# fpga-ground-inside.net
KiCad netlist of a schematic drawn in Altium Designer
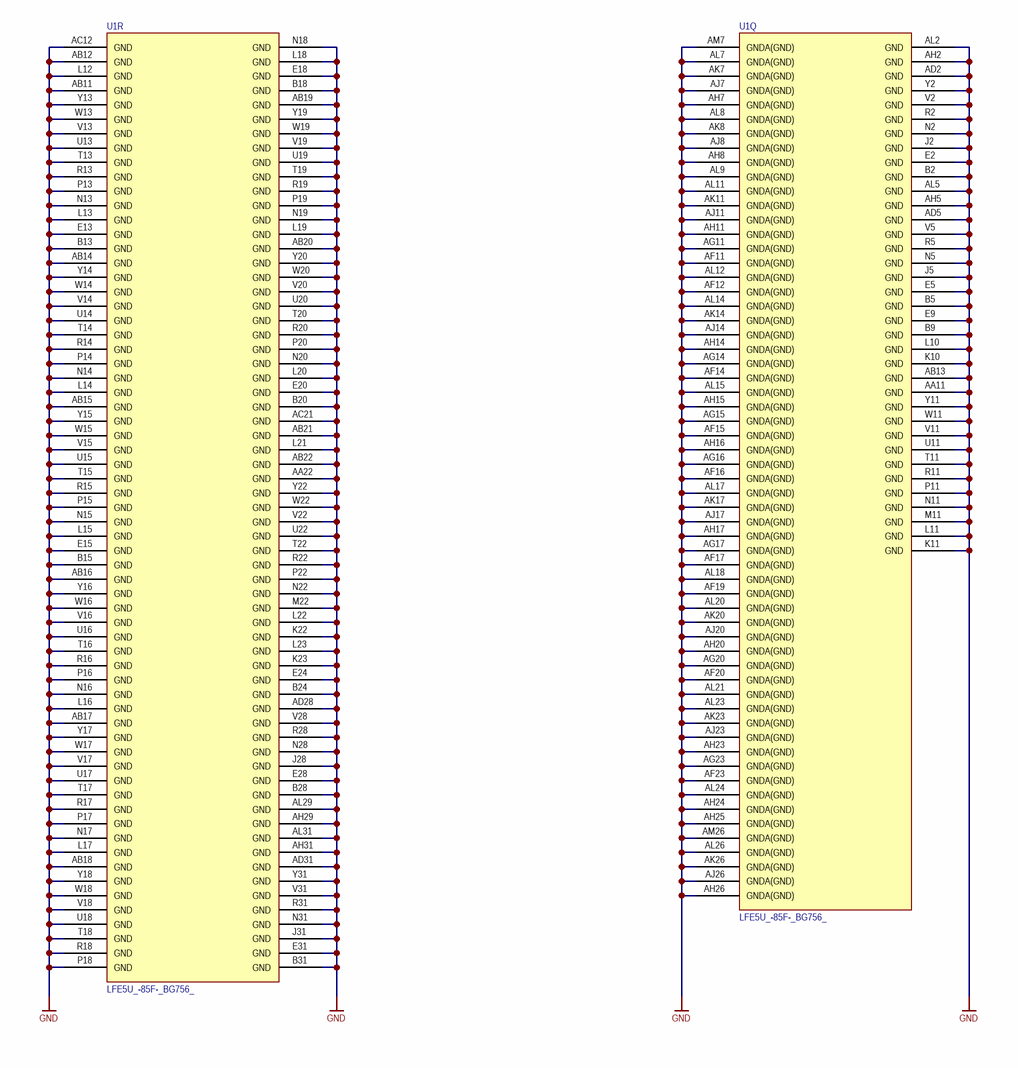
[diagram p0: fpga-ground-inside.SchDoc]

(export (version "E")
  (design (tool "Eeschema 10.0.6"))
  (components
    (comp (ref "U1")
      (value "LFE5U_-85F-_BG756_")
      (footprint "lattice:caBGA756")
      (description "ECP5 FPGA, 85k LUT, 756-caBGA")
      (fields (field (name "MANUFACTURER") "Lattice Semiconductor"))
      (libsource (lib "lattice") (part "LFE5U_-85F-_BG756_"))
    )
  )
  (nets
    (net (code "1") (name "GND") (class "Default")
      (node (ref "U1") (pin "AA11") (pinfunction "GND_AA11") (pintype "power_in"))
      (node (ref "U1") (pin "AA22") (pinfunction "GND_AA22") (pintype "power_in"))
      (node (ref "U1") (pin "AB11") (pinfunction "GND_AB11") (pintype "power_in"))
      (node (ref "U1") (pin "AB12") (pinfunction "GND_AB12") (pintype "power_in"))
      (node (ref "U1") (pin "AB13") (pinfunction "GND_AB13") (pintype "power_in"))
      (node (ref "U1") (pin "AB14") (pinfunction "GND_AB14") (pintype "power_in"))
      (node (ref "U1") (pin "AB15") (pinfunction "GND_AB15") (pintype "power_in"))
      (node (ref "U1") (pin "AB16") (pinfunction "GND_AB16") (pintype "power_in"))
      (node (ref "U1") (pin "AB17") (pinfunction "GND_AB17") (pintype "power_in"))
      (node (ref "U1") (pin "AB18") (pinfunction "GND_AB18") (pintype "power_in"))
      (node (ref "U1") (pin "AB19") (pinfunction "GND_AB19") (pintype "power_in"))
      (node (ref "U1") (pin "AB20") (pinfunction "GND_AB20") (pintype "power_in"))
      (node (ref "U1") (pin "AB21") (pinfunction "GND_AB21") (pintype "power_in"))
      (node (ref "U1") (pin "AB22") (pinfunction "GND_AB22") (pintype "power_in"))
      (node (ref "U1") (pin "AC12") (pinfunction "GND_AC12") (pintype "power_in"))
      (node (ref "U1") (pin "AC21") (pinfunction "GND_AC21") (pintype "power_in"))
      (node (ref "U1") (pin "AD2") (pinfunction "GND_AD2") (pintype "power_in"))
      (node (ref "U1") (pin "AD28") (pinfunction "GND_AD28") (pintype "power_in"))
      (node (ref "U1") (pin "AD31") (pinfunction "GND_AD31") (pintype "power_in"))
      (node (ref "U1") (pin "AD5") (pinfunction "GND_AD5") (pintype "power_in"))
      (node (ref "U1") (pin "AF11") (pinfunction "GNDA(GND)_AF11") (pintype "power_in"))
      (node (ref "U1") (pin "AF12") (pinfunction "GNDA(GND)_AF12") (pintype "power_in"))
      (node (ref "U1") (pin "AF14") (pinfunction "GNDA(GND)_AF14") (pintype "power_in"))
      (node (ref "U1") (pin "AF15") (pinfunction "GNDA(GND)_AF15") (pintype "power_in"))
      (node (ref "U1") (pin "AF16") (pinfunction "GNDA(GND)_AF16") (pintype "power_in"))
      (node (ref "U1") (pin "AF17") (pinfunction "GNDA(GND)_AF17") (pintype "power_in"))
      (node (ref "U1") (pin "AF19") (pinfunction "GNDA(GND)_AF19") (pintype "power_in"))
      (node (ref "U1") (pin "AF20") (pinfunction "GNDA(GND)_AF20") (pintype "power_in"))
      (node (ref "U1") (pin "AF23") (pinfunction "GNDA(GND)_AF23") (pintype "power_in"))
      (node (ref "U1") (pin "AG11") (pinfunction "GNDA(GND)_AG11") (pintype "power_in"))
      (node (ref "U1") (pin "AG14") (pinfunction "GNDA(GND)_AG14") (pintype "power_in"))
      (node (ref "U1") (pin "AG15") (pinfunction "GNDA(GND)_AG15") (pintype "power_in"))
      (node (ref "U1") (pin "AG16") (pinfunction "GNDA(GND)_AG16") (pintype "power_in"))
      (node (ref "U1") (pin "AG17") (pinfunction "GNDA(GND)_AG17") (pintype "power_in"))
      (node (ref "U1") (pin "AG20") (pinfunction "GNDA(GND)_AG20") (pintype "power_in"))
      (node (ref "U1") (pin "AG23") (pinfunction "GNDA(GND)_AG23") (pintype "power_in"))
      (node (ref "U1") (pin "AH11") (pinfunction "GNDA(GND)_AH11") (pintype "power_in"))
      (node (ref "U1") (pin "AH14") (pinfunction "GNDA(GND)_AH14") (pintype "power_in"))
      (node (ref "U1") (pin "AH15") (pinfunction "GNDA(GND)_AH15") (pintype "power_in"))
      (node (ref "U1") (pin "AH16") (pinfunction "GNDA(GND)_AH16") (pintype "power_in"))
      (node (ref "U1") (pin "AH17") (pinfunction "GNDA(GND)_AH17") (pintype "power_in"))
      (node (ref "U1") (pin "AH2") (pinfunction "GND_AH2") (pintype "power_in"))
      (node (ref "U1") (pin "AH20") (pinfunction "GNDA(GND)_AH20") (pintype "power_in"))
      (node (ref "U1") (pin "AH23") (pinfunction "GNDA(GND)_AH23") (pintype "power_in"))
      (node (ref "U1") (pin "AH24") (pinfunction "GNDA(GND)_AH24") (pintype "power_in"))
      (node (ref "U1") (pin "AH25") (pinfunction "GNDA(GND)_AH25") (pintype "power_in"))
      (node (ref "U1") (pin "AH26") (pinfunction "GNDA(GND)_AH26") (pintype "power_in"))
      (node (ref "U1") (pin "AH29") (pinfunction "GND_AH29") (pintype "power_in"))
      (node (ref "U1") (pin "AH31") (pinfunction "GND_AH31") (pintype "power_in"))
      (node (ref "U1") (pin "AH5") (pinfunction "GND_AH5") (pintype "power_in"))
      (node (ref "U1") (pin "AH7") (pinfunction "GNDA(GND)_AH7") (pintype "power_in"))
      (node (ref "U1") (pin "AH8") (pinfunction "GNDA(GND)_AH8") (pintype "power_in"))
      (node (ref "U1") (pin "AJ11") (pinfunction "GNDA(GND)_AJ11") (pintype "power_in"))
      (node (ref "U1") (pin "AJ14") (pinfunction "GNDA(GND)_AJ14") (pintype "power_in"))
      (node (ref "U1") (pin "AJ17") (pinfunction "GNDA(GND)_AJ17") (pintype "power_in"))
      (node (ref "U1") (pin "AJ20") (pinfunction "GNDA(GND)_AJ20") (pintype "power_in"))
      (node (ref "U1") (pin "AJ23") (pinfunction "GNDA(GND)_AJ23") (pintype "power_in"))
      (node (ref "U1") (pin "AJ26") (pinfunction "GNDA(GND)_AJ26") (pintype "power_in"))
      (node (ref "U1") (pin "AJ7") (pinfunction "GNDA(GND)_AJ7") (pintype "power_in"))
      (node (ref "U1") (pin "AJ8") (pinfunction "GNDA(GND)_AJ8") (pintype "power_in"))
      (node (ref "U1") (pin "AK11") (pinfunction "GNDA(GND)_AK11") (pintype "power_in"))
      (node (ref "U1") (pin "AK14") (pinfunction "GNDA(GND)_AK14") (pintype "power_in"))
      (node (ref "U1") (pin "AK17") (pinfunction "GNDA(GND)_AK17") (pintype "power_in"))
      (node (ref "U1") (pin "AK20") (pinfunction "GNDA(GND)_AK20") (pintype "power_in"))
      (node (ref "U1") (pin "AK23") (pinfunction "GNDA(GND)_AK23") (pintype "power_in"))
      (node (ref "U1") (pin "AK26") (pinfunction "GNDA(GND)_AK26") (pintype "power_in"))
      (node (ref "U1") (pin "AK7") (pinfunction "GNDA(GND)_AK7") (pintype "power_in"))
      (node (ref "U1") (pin "AK8") (pinfunction "GNDA(GND)_AK8") (pintype "power_in"))
      (node (ref "U1") (pin "AL11") (pinfunction "GNDA(GND)_AL11") (pintype "power_in"))
      (node (ref "U1") (pin "AL12") (pinfunction "GNDA(GND)_AL12") (pintype "power_in"))
      (node (ref "U1") (pin "AL14") (pinfunction "GNDA(GND)_AL14") (pintype "power_in"))
      (node (ref "U1") (pin "AL15") (pinfunction "GNDA(GND)_AL15") (pintype "power_in"))
      (node (ref "U1") (pin "AL17") (pinfunction "GNDA(GND)_AL17") (pintype "power_in"))
      (node (ref "U1") (pin "AL18") (pinfunction "GNDA(GND)_AL18") (pintype "power_in"))
      (node (ref "U1") (pin "AL2") (pinfunction "GND_AL2") (pintype "power_in"))
      (node (ref "U1") (pin "AL20") (pinfunction "GNDA(GND)_AL20") (pintype "power_in"))
      (node (ref "U1") (pin "AL21") (pinfunction "GNDA(GND)_AL21") (pintype "power_in"))
      (node (ref "U1") (pin "AL23") (pinfunction "GNDA(GND)_AL23") (pintype "power_in"))
      (node (ref "U1") (pin "AL24") (pinfunction "GNDA(GND)_AL24") (pintype "power_in"))
      (node (ref "U1") (pin "AL26") (pinfunction "GNDA(GND)_AL26") (pintype "power_in"))
      (node (ref "U1") (pin "AL29") (pinfunction "GND_AL29") (pintype "power_in"))
      (node (ref "U1") (pin "AL31") (pinfunction "GND_AL31") (pintype "power_in"))
      (node (ref "U1") (pin "AL5") (pinfunction "GND_AL5") (pintype "power_in"))
      (node (ref "U1") (pin "AL7") (pinfunction "GNDA(GND)_AL7") (pintype "power_in"))
      (node (ref "U1") (pin "AL8") (pinfunction "GNDA(GND)_AL8") (pintype "power_in"))
      (node (ref "U1") (pin "AL9") (pinfunction "GNDA(GND)_AL9") (pintype "power_in"))
      (node (ref "U1") (pin "AM26") (pinfunction "GNDA(GND)_AM26") (pintype "power_in"))
      (node (ref "U1") (pin "AM7") (pinfunction "GNDA(GND)_AM7") (pintype "power_in"))
      (node (ref "U1") (pin "B13") (pinfunction "GND_B13") (pintype "power_in"))
      (node (ref "U1") (pin "B15") (pinfunction "GND_B15") (pintype "power_in"))
      (node (ref "U1") (pin "B18") (pinfunction "GND_B18") (pintype "power_in"))
      (node (ref "U1") (pin "B2") (pinfunction "GND_B2") (pintype "power_in"))
      (node (ref "U1") (pin "B20") (pinfunction "GND_B20") (pintype "power_in"))
      (node (ref "U1") (pin "B24") (pinfunction "GND_B24") (pintype "power_in"))
      (node (ref "U1") (pin "B28") (pinfunction "GND_B28") (pintype "power_in"))
      (node (ref "U1") (pin "B31") (pinfunction "GND_B31") (pintype "power_in"))
      (node (ref "U1") (pin "B5") (pinfunction "GND_B5") (pintype "power_in"))
      (node (ref "U1") (pin "B9") (pinfunction "GND_B9") (pintype "power_in"))
      (node (ref "U1") (pin "E13") (pinfunction "GND_E13") (pintype "power_in"))
      (node (ref "U1") (pin "E15") (pinfunction "GND_E15") (pintype "power_in"))
      (node (ref "U1") (pin "E18") (pinfunction "GND_E18") (pintype "power_in"))
      (node (ref "U1") (pin "E2") (pinfunction "GND_E2") (pintype "power_in"))
      (node (ref "U1") (pin "E20") (pinfunction "GND_E20") (pintype "power_in"))
      (node (ref "U1") (pin "E24") (pinfunction "GND_E24") (pintype "power_in"))
      (node (ref "U1") (pin "E28") (pinfunction "GND_E28") (pintype "power_in"))
      (node (ref "U1") (pin "E31") (pinfunction "GND_E31") (pintype "power_in"))
      (node (ref "U1") (pin "E5") (pinfunction "GND_E5") (pintype "power_in"))
      (node (ref "U1") (pin "E9") (pinfunction "GND_E9") (pintype "power_in"))
      (node (ref "U1") (pin "J2") (pinfunction "GND_J2") (pintype "power_in"))
      (node (ref "U1") (pin "J28") (pinfunction "GND_J28") (pintype "power_in"))
      (node (ref "U1") (pin "J31") (pinfunction "GND_J31") (pintype "power_in"))
      (node (ref "U1") (pin "J5") (pinfunction "GND_J5") (pintype "power_in"))
      (node (ref "U1") (pin "K10") (pinfunction "GND_K10") (pintype "power_in"))
      (node (ref "U1") (pin "K11") (pinfunction "GND_K11") (pintype "power_in"))
      (node (ref "U1") (pin "K22") (pinfunction "GND_K22") (pintype "power_in"))
      (node (ref "U1") (pin "K23") (pinfunction "GND_K23") (pintype "power_in"))
      (node (ref "U1") (pin "L10") (pinfunction "GND_L10") (pintype "power_in"))
      (node (ref "U1") (pin "L11") (pinfunction "GND_L11") (pintype "power_in"))
      (node (ref "U1") (pin "L12") (pinfunction "GND_L12") (pintype "power_in"))
      (node (ref "U1") (pin "L13") (pinfunction "GND_L13") (pintype "power_in"))
      (node (ref "U1") (pin "L14") (pinfunction "GND_L14") (pintype "power_in"))
      (node (ref "U1") (pin "L15") (pinfunction "GND_L15") (pintype "power_in"))
      (node (ref "U1") (pin "L16") (pinfunction "GND_L16") (pintype "power_in"))
      (node (ref "U1") (pin "L17") (pinfunction "GND_L17") (pintype "power_in"))
      (node (ref "U1") (pin "L18") (pinfunction "GND_L18") (pintype "power_in"))
      (node (ref "U1") (pin "L19") (pinfunction "GND_L19") (pintype "power_in"))
      (node (ref "U1") (pin "L20") (pinfunction "GND_L20") (pintype "power_in"))
      (node (ref "U1") (pin "L21") (pinfunction "GND_L21") (pintype "power_in"))
      (node (ref "U1") (pin "L22") (pinfunction "GND_L22") (pintype "power_in"))
      (node (ref "U1") (pin "L23") (pinfunction "GND_L23") (pintype "power_in"))
      (node (ref "U1") (pin "M11") (pinfunction "GND_M11") (pintype "power_in"))
      (node (ref "U1") (pin "M22") (pinfunction "GND_M22") (pintype "power_in"))
      (node (ref "U1") (pin "N11") (pinfunction "GND_N11") (pintype "power_in"))
      (node (ref "U1") (pin "N13") (pinfunction "GND_N13") (pintype "power_in"))
      (node (ref "U1") (pin "N14") (pinfunction "GND_N14") (pintype "power_in"))
      (node (ref "U1") (pin "N15") (pinfunction "GND_N15") (pintype "power_in"))
      (node (ref "U1") (pin "N16") (pinfunction "GND_N16") (pintype "power_in"))
      (node (ref "U1") (pin "N17") (pinfunction "GND_N17") (pintype "power_in"))
      (node (ref "U1") (pin "N18") (pinfunction "GND_N18") (pintype "power_in"))
      (node (ref "U1") (pin "N19") (pinfunction "GND_N19") (pintype "power_in"))
      (node (ref "U1") (pin "N2") (pinfunction "GND_N2") (pintype "power_in"))
      (node (ref "U1") (pin "N20") (pinfunction "GND_N20") (pintype "power_in"))
      (node (ref "U1") (pin "N22") (pinfunction "GND_N22") (pintype "power_in"))
      (node (ref "U1") (pin "N28") (pinfunction "GND_N28") (pintype "power_in"))
      (node (ref "U1") (pin "N31") (pinfunction "GND_N31") (pintype "power_in"))
      (node (ref "U1") (pin "N5") (pinfunction "GND_N5") (pintype "power_in"))
      (node (ref "U1") (pin "P11") (pinfunction "GND_P11") (pintype "power_in"))
      (node (ref "U1") (pin "P13") (pinfunction "GND_P13") (pintype "power_in"))
      (node (ref "U1") (pin "P14") (pinfunction "GND_P14") (pintype "power_in"))
      (node (ref "U1") (pin "P15") (pinfunction "GND_P15") (pintype "power_in"))
      (node (ref "U1") (pin "P16") (pinfunction "GND_P16") (pintype "power_in"))
      (node (ref "U1") (pin "P17") (pinfunction "GND_P17") (pintype "power_in"))
      (node (ref "U1") (pin "P18") (pinfunction "GND_P18") (pintype "power_in"))
      (node (ref "U1") (pin "P19") (pinfunction "GND_P19") (pintype "power_in"))
      (node (ref "U1") (pin "P20") (pinfunction "GND_P20") (pintype "power_in"))
      (node (ref "U1") (pin "P22") (pinfunction "GND_P22") (pintype "power_in"))
      (node (ref "U1") (pin "R11") (pinfunction "GND_R11") (pintype "power_in"))
      (node (ref "U1") (pin "R13") (pinfunction "GND_R13") (pintype "power_in"))
      (node (ref "U1") (pin "R14") (pinfunction "GND_R14") (pintype "power_in"))
      (node (ref "U1") (pin "R15") (pinfunction "GND_R15") (pintype "power_in"))
      (node (ref "U1") (pin "R16") (pinfunction "GND_R16") (pintype "power_in"))
      (node (ref "U1") (pin "R17") (pinfunction "GND_R17") (pintype "power_in"))
      (node (ref "U1") (pin "R18") (pinfunction "GND_R18") (pintype "power_in"))
      (node (ref "U1") (pin "R19") (pinfunction "GND_R19") (pintype "power_in"))
      (node (ref "U1") (pin "R2") (pinfunction "GND_R2") (pintype "power_in"))
      (node (ref "U1") (pin "R20") (pinfunction "GND_R20") (pintype "power_in"))
      (node (ref "U1") (pin "R22") (pinfunction "GND_R22") (pintype "power_in"))
      (node (ref "U1") (pin "R28") (pinfunction "GND_R28") (pintype "power_in"))
      (node (ref "U1") (pin "R31") (pinfunction "GND_R31") (pintype "power_in"))
      (node (ref "U1") (pin "R5") (pinfunction "GND_R5") (pintype "power_in"))
      (node (ref "U1") (pin "T11") (pinfunction "GND_T11") (pintype "power_in"))
      (node (ref "U1") (pin "T13") (pinfunction "GND_T13") (pintype "power_in"))
      (node (ref "U1") (pin "T14") (pinfunction "GND_T14") (pintype "power_in"))
      (node (ref "U1") (pin "T15") (pinfunction "GND_T15") (pintype "power_in"))
      (node (ref "U1") (pin "T16") (pinfunction "GND_T16") (pintype "power_in"))
      (node (ref "U1") (pin "T17") (pinfunction "GND_T17") (pintype "power_in"))
      (node (ref "U1") (pin "T18") (pinfunction "GND_T18") (pintype "power_in"))
      (node (ref "U1") (pin "T19") (pinfunction "GND_T19") (pintype "power_in"))
      (node (ref "U1") (pin "T20") (pinfunction "GND_T20") (pintype "power_in"))
      (node (ref "U1") (pin "T22") (pinfunction "GND_T22") (pintype "power_in"))
      (node (ref "U1") (pin "U11") (pinfunction "GND_U11") (pintype "power_in"))
      (node (ref "U1") (pin "U13") (pinfunction "GND_U13") (pintype "power_in"))
      (node (ref "U1") (pin "U14") (pinfunction "GND_U14") (pintype "power_in"))
      (node (ref "U1") (pin "U15") (pinfunction "GND_U15") (pintype "power_in"))
      (node (ref "U1") (pin "U16") (pinfunction "GND_U16") (pintype "power_in"))
      (node (ref "U1") (pin "U17") (pinfunction "GND_U17") (pintype "power_in"))
      (node (ref "U1") (pin "U18") (pinfunction "GND_U18") (pintype "power_in"))
      (node (ref "U1") (pin "U19") (pinfunction "GND_U19") (pintype "power_in"))
      (node (ref "U1") (pin "U20") (pinfunction "GND_U20") (pintype "power_in"))
      (node (ref "U1") (pin "U22") (pinfunction "GND_U22") (pintype "power_in"))
      (node (ref "U1") (pin "V11") (pinfunction "GND_V11") (pintype "power_in"))
      (node (ref "U1") (pin "V13") (pinfunction "GND_V13") (pintype "power_in"))
      (node (ref "U1") (pin "V14") (pinfunction "GND_V14") (pintype "power_in"))
      (node (ref "U1") (pin "V15") (pinfunction "GND_V15") (pintype "power_in"))
      (node (ref "U1") (pin "V16") (pinfunction "GND_V16") (pintype "power_in"))
      (node (ref "U1") (pin "V17") (pinfunction "GND_V17") (pintype "power_in"))
      (node (ref "U1") (pin "V18") (pinfunction "GND_V18") (pintype "power_in"))
      (node (ref "U1") (pin "V19") (pinfunction "GND_V19") (pintype "power_in"))
      (node (ref "U1") (pin "V2") (pinfunction "GND_V2") (pintype "power_in"))
      (node (ref "U1") (pin "V20") (pinfunction "GND_V20") (pintype "power_in"))
      (node (ref "U1") (pin "V22") (pinfunction "GND_V22") (pintype "power_in"))
      (node (ref "U1") (pin "V28") (pinfunction "GND_V28") (pintype "power_in"))
      (node (ref "U1") (pin "V31") (pinfunction "GND_V31") (pintype "power_in"))
      (node (ref "U1") (pin "V5") (pinfunction "GND_V5") (pintype "power_in"))
      (node (ref "U1") (pin "W11") (pinfunction "GND_W11") (pintype "power_in"))
      (node (ref "U1") (pin "W13") (pinfunction "GND_W13") (pintype "power_in"))
      (node (ref "U1") (pin "W14") (pinfunction "GND_W14") (pintype "power_in"))
      (node (ref "U1") (pin "W15") (pinfunction "GND_W15") (pintype "power_in"))
      (node (ref "U1") (pin "W16") (pinfunction "GND_W16") (pintype "power_in"))
      (node (ref "U1") (pin "W17") (pinfunction "GND_W17") (pintype "power_in"))
      (node (ref "U1") (pin "W18") (pinfunction "GND_W18") (pintype "power_in"))
      (node (ref "U1") (pin "W19") (pinfunction "GND_W19") (pintype "power_in"))
      (node (ref "U1") (pin "W20") (pinfunction "GND_W20") (pintype "power_in"))
      (node (ref "U1") (pin "W22") (pinfunction "GND_W22") (pintype "power_in"))
      (node (ref "U1") (pin "Y11") (pinfunction "GND_Y11") (pintype "power_in"))
      (node (ref "U1") (pin "Y13") (pinfunction "GND_Y13") (pintype "power_in"))
      (node (ref "U1") (pin "Y14") (pinfunction "GND_Y14") (pintype "power_in"))
      (node (ref "U1") (pin "Y15") (pinfunction "GND_Y15") (pintype "power_in"))
      (node (ref "U1") (pin "Y16") (pinfunction "GND_Y16") (pintype "power_in"))
      (node (ref "U1") (pin "Y17") (pinfunction "GND_Y17") (pintype "power_in"))
      (node (ref "U1") (pin "Y18") (pinfunction "GND_Y18") (pintype "power_in"))
      (node (ref "U1") (pin "Y19") (pinfunction "GND_Y19") (pintype "power_in"))
      (node (ref "U1") (pin "Y2") (pinfunction "GND_Y2") (pintype "power_in"))
      (node (ref "U1") (pin "Y20") (pinfunction "GND_Y20") (pintype "power_in"))
      (node (ref "U1") (pin "Y22") (pinfunction "GND_Y22") (pintype "power_in"))
      (node (ref "U1") (pin "Y31") (pinfunction "GND_Y31") (pintype "power_in"))
    )
  )
)
